# led_panel.net
KiCad netlist of a schematic drawn in EAGLE
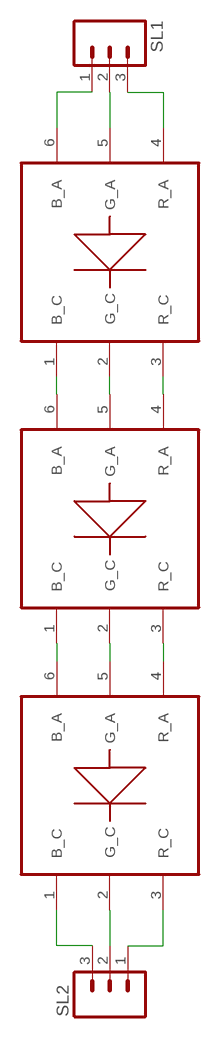
[diagram p0: schematic, sheet 1]

(export (version "E")
  (design (tool "Eeschema 10.0.6"))
  (components
    (comp (ref "SL1")
      (value "M03")
      (footprint "eagle-import:03P")
      (libsource (lib "eagle-import") (part "M03"))
    )
    (comp (ref "SL2")
      (value "M03")
      (footprint "eagle-import:03P")
      (libsource (lib "eagle-import") (part "M03"))
    )
    (comp (ref "U$1")
      (value "RGB_SMD_3W")
      (footprint "eagle-import:RGB_SMD_6PIN")
      (libsource (lib "eagle-import") (part "RGB_SMD_3W"))
    )
    (comp (ref "U$2")
      (value "RGB_SMD_3W")
      (footprint "eagle-import:RGB_SMD_6PIN")
      (libsource (lib "eagle-import") (part "RGB_SMD_3W"))
    )
    (comp (ref "U$3")
      (value "RGB_SMD_3W")
      (footprint "eagle-import:RGB_SMD_6PIN")
      (libsource (lib "eagle-import") (part "RGB_SMD_3W"))
    )
  )
  (nets
    (net (code "1") (name "Net-(U$1-B_A)") (class "Default")
      (node (ref "SL1") (pin "1") (pinfunction "1_1") (pintype "passive"))
      (node (ref "U$1") (pin "6") (pinfunction "B_A_6") (pintype "passive"))
    )
    (net (code "2") (name "Net-(U$1-B_C)") (class "Default")
      (node (ref "U$1") (pin "1") (pinfunction "B_C_1") (pintype "passive"))
      (node (ref "U$2") (pin "6") (pinfunction "B_A_6") (pintype "passive"))
    )
    (net (code "3") (name "Net-(U$1-G_A)") (class "Default")
      (node (ref "SL1") (pin "2") (pinfunction "2_2") (pintype "passive"))
      (node (ref "U$1") (pin "5") (pinfunction "G_A_5") (pintype "passive"))
    )
    (net (code "4") (name "Net-(U$1-G_C)") (class "Default")
      (node (ref "U$1") (pin "2") (pinfunction "G_C_2") (pintype "passive"))
      (node (ref "U$2") (pin "5") (pinfunction "G_A_5") (pintype "passive"))
    )
    (net (code "5") (name "Net-(U$1-R_A)") (class "Default")
      (node (ref "SL1") (pin "3") (pinfunction "3_3") (pintype "passive"))
      (node (ref "U$1") (pin "4") (pinfunction "R_A_4") (pintype "passive"))
    )
    (net (code "6") (name "Net-(U$1-R_C)") (class "Default")
      (node (ref "U$1") (pin "3") (pinfunction "R_C_3") (pintype "passive"))
      (node (ref "U$2") (pin "4") (pinfunction "R_A_4") (pintype "passive"))
    )
    (net (code "7") (name "Net-(U$2-B_C)") (class "Default")
      (node (ref "U$2") (pin "1") (pinfunction "B_C_1") (pintype "passive"))
      (node (ref "U$3") (pin "6") (pinfunction "B_A_6") (pintype "passive"))
    )
    (net (code "8") (name "Net-(U$2-G_C)") (class "Default")
      (node (ref "U$2") (pin "2") (pinfunction "G_C_2") (pintype "passive"))
      (node (ref "U$3") (pin "5") (pinfunction "G_A_5") (pintype "passive"))
    )
    (net (code "9") (name "Net-(U$2-R_C)") (class "Default")
      (node (ref "U$2") (pin "3") (pinfunction "R_C_3") (pintype "passive"))
      (node (ref "U$3") (pin "4") (pinfunction "R_A_4") (pintype "passive"))
    )
    (net (code "10") (name "Net-(U$3-B_C)") (class "Default")
      (node (ref "SL2") (pin "3") (pinfunction "3_3") (pintype "passive"))
      (node (ref "U$3") (pin "1") (pinfunction "B_C_1") (pintype "passive"))
    )
    (net (code "11") (name "Net-(U$3-G_C)") (class "Default")
      (node (ref "SL2") (pin "2") (pinfunction "2_2") (pintype "passive"))
      (node (ref "U$3") (pin "2") (pinfunction "G_C_2") (pintype "passive"))
    )
    (net (code "12") (name "Net-(U$3-R_C)") (class "Default")
      (node (ref "SL2") (pin "1") (pinfunction "1_1") (pintype "passive"))
      (node (ref "U$3") (pin "3") (pinfunction "R_C_3") (pintype "passive"))
    )
  )
)
